# Pico.net
KiCad netlist of a schematic drawn in Altium Designer
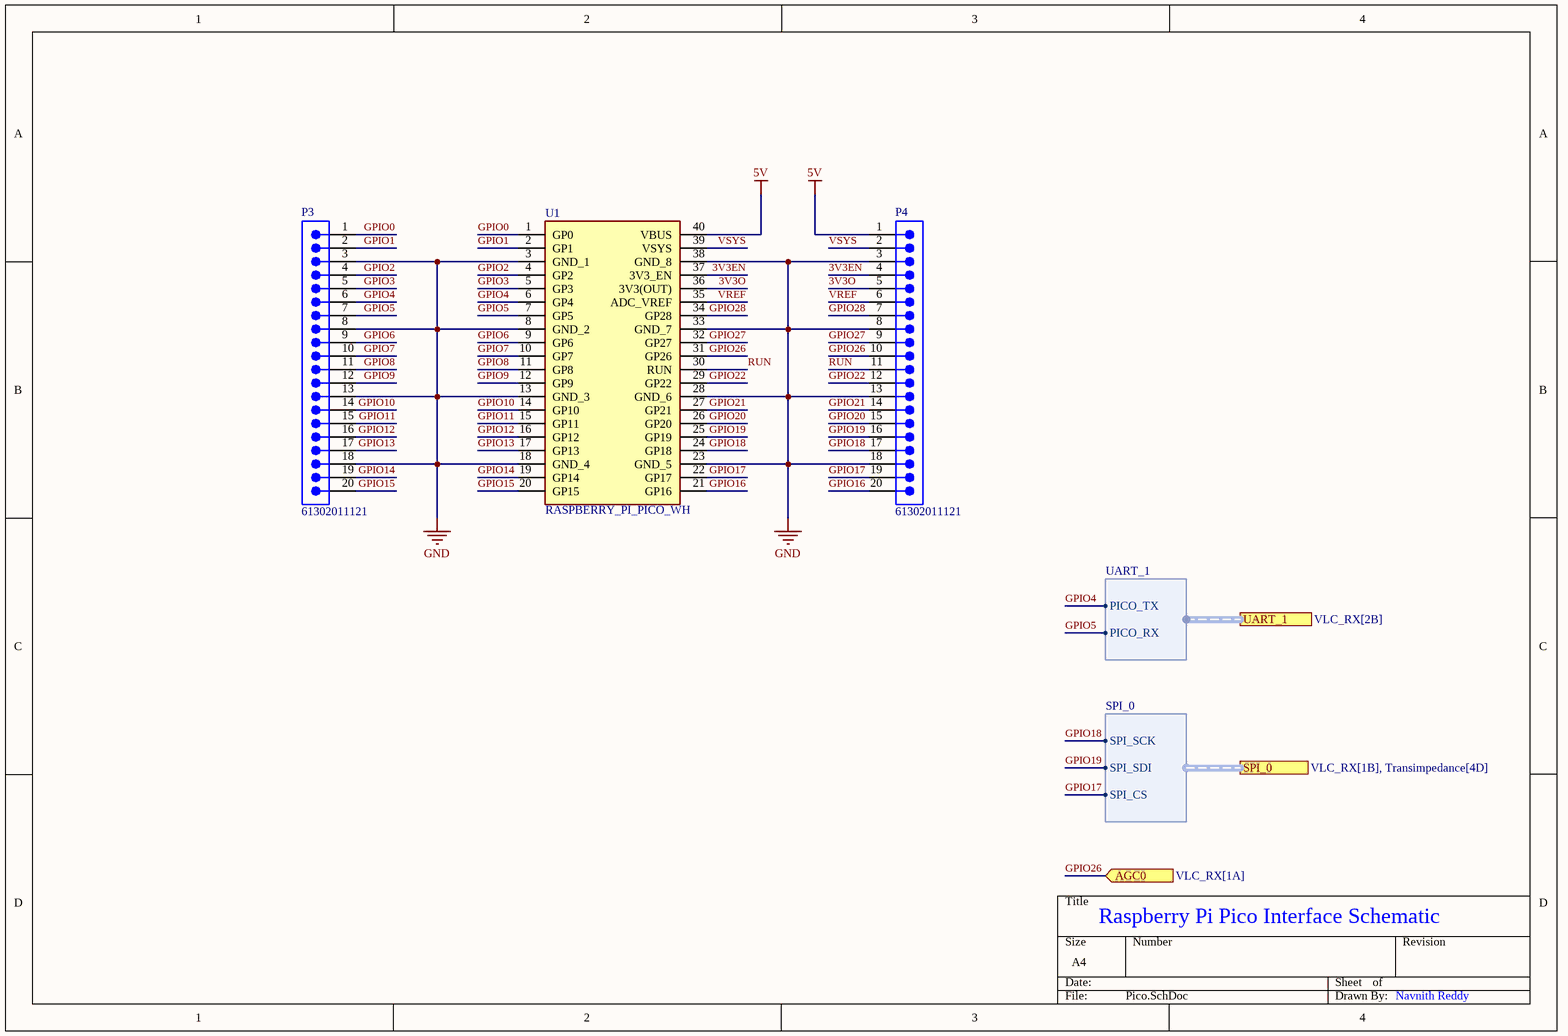
[diagram p0: Pico.SchDoc]

(export (version "E")
  (design (tool "Eeschema 10.0.6"))
  (components
    (comp (ref "P3")
      (value "61302011121")
      (footprint "61302011121")
      (libsource (lib "Altium Content Vault") (part "Header_Male_1R_20P"))
    )
    (comp (ref "P4")
      (value "61302011121")
      (footprint "61302011121")
      (libsource (lib "Altium Content Vault") (part "Header_Male_1R_20P"))
    )
    (comp (ref "U1")
      (value "RASPBERRY_PI_PICO_WH")
      (footprint "SamacSys:RASPBERRYPIPICOWH")
      (description "Undefined or Miscellaneous")
      (fields (field (name "MANUFACTURER_PART_NUMBER") "RASPBERRY PI PICO WH"))
      (libsource (lib "*") (part "RASPBERRY_PI_PICO_WH"))
    )
  )
  (nets
    (net (code "3") (name "/3V3EN") (class "Default")
      (node (ref "P4") (pin "4") (pinfunction "4_4") (pintype "passive"))
      (node (ref "U1") (pin "37") (pinfunction "3V3_EN_37") (pintype "passive"))
    )
    (net (code "4") (name "/3V3O") (class "Default")
      (node (ref "P4") (pin "5") (pinfunction "5_5") (pintype "passive"))
      (node (ref "U1") (pin "36") (pinfunction "3V3(OUT)_36") (pintype "passive"))
    )
    (net (code "5") (name "/GPIO0") (class "Default")
      (node (ref "P3") (pin "1") (pinfunction "1_1") (pintype "passive"))
      (node (ref "U1") (pin "1") (pinfunction "GP0_1") (pintype "passive"))
    )
    (net (code "6") (name "/GPIO1") (class "Default")
      (node (ref "P3") (pin "2") (pinfunction "2_2") (pintype "passive"))
      (node (ref "U1") (pin "2") (pinfunction "GP1_2") (pintype "passive"))
    )
    (net (code "7") (name "/GPIO2") (class "Default")
      (node (ref "P3") (pin "4") (pinfunction "4_4") (pintype "passive"))
      (node (ref "U1") (pin "4") (pinfunction "GP2_4") (pintype "passive"))
    )
    (net (code "8") (name "/GPIO3") (class "Default")
      (node (ref "P3") (pin "5") (pinfunction "5_5") (pintype "passive"))
      (node (ref "U1") (pin "5") (pinfunction "GP3_5") (pintype "passive"))
    )
    (net (code "9") (name "/GPIO4") (class "Default")
      (node (ref "P3") (pin "6") (pinfunction "6_6") (pintype "passive"))
      (node (ref "U1") (pin "6") (pinfunction "GP4_6") (pintype "passive"))
    )
    (net (code "10") (name "/GPIO5") (class "Default")
      (node (ref "P3") (pin "7") (pinfunction "7_7") (pintype "passive"))
      (node (ref "U1") (pin "7") (pinfunction "GP5_7") (pintype "passive"))
    )
    (net (code "11") (name "/GPIO6") (class "Default")
      (node (ref "P3") (pin "9") (pinfunction "9_9") (pintype "passive"))
      (node (ref "U1") (pin "9") (pinfunction "GP6_9") (pintype "passive"))
    )
    (net (code "12") (name "/GPIO7") (class "Default")
      (node (ref "P3") (pin "10") (pinfunction "10_10") (pintype "passive"))
      (node (ref "U1") (pin "10") (pinfunction "GP7_10") (pintype "passive"))
    )
    (net (code "13") (name "/GPIO8") (class "Default")
      (node (ref "P3") (pin "11") (pinfunction "11_11") (pintype "passive"))
      (node (ref "U1") (pin "11") (pinfunction "GP8_11") (pintype "passive"))
    )
    (net (code "14") (name "/GPIO9") (class "Default")
      (node (ref "P3") (pin "12") (pinfunction "12_12") (pintype "passive"))
      (node (ref "U1") (pin "12") (pinfunction "GP9_12") (pintype "passive"))
    )
    (net (code "15") (name "/GPIO10") (class "Default")
      (node (ref "P3") (pin "14") (pinfunction "14_14") (pintype "passive"))
      (node (ref "U1") (pin "14") (pinfunction "GP10_14") (pintype "passive"))
    )
    (net (code "16") (name "/GPIO11") (class "Default")
      (node (ref "P3") (pin "15") (pinfunction "15_15") (pintype "passive"))
      (node (ref "U1") (pin "15") (pinfunction "GP11_15") (pintype "passive"))
    )
    (net (code "17") (name "/GPIO12") (class "Default")
      (node (ref "P3") (pin "16") (pinfunction "16_16") (pintype "passive"))
      (node (ref "U1") (pin "16") (pinfunction "GP12_16") (pintype "passive"))
    )
    (net (code "18") (name "/GPIO13") (class "Default")
      (node (ref "P3") (pin "17") (pinfunction "17_17") (pintype "passive"))
      (node (ref "U1") (pin "17") (pinfunction "GP13_17") (pintype "passive"))
    )
    (net (code "19") (name "/GPIO14") (class "Default")
      (node (ref "P3") (pin "19") (pinfunction "19_19") (pintype "passive"))
      (node (ref "U1") (pin "19") (pinfunction "GP14_19") (pintype "passive"))
    )
    (net (code "20") (name "/GPIO15") (class "Default")
      (node (ref "P3") (pin "20") (pinfunction "20_20") (pintype "passive"))
      (node (ref "U1") (pin "20") (pinfunction "GP15_20") (pintype "passive"))
    )
    (net (code "21") (name "/GPIO16") (class "Default")
      (node (ref "P4") (pin "20") (pinfunction "20_20") (pintype "passive"))
      (node (ref "U1") (pin "21") (pinfunction "GP16_21") (pintype "passive"))
    )
    (net (code "22") (name "/GPIO17") (class "Default")
      (node (ref "P4") (pin "19") (pinfunction "19_19") (pintype "passive"))
      (node (ref "U1") (pin "22") (pinfunction "GP17_22") (pintype "passive"))
    )
    (net (code "23") (name "/GPIO18") (class "Default")
      (node (ref "P4") (pin "17") (pinfunction "17_17") (pintype "passive"))
      (node (ref "U1") (pin "24") (pinfunction "GP18_24") (pintype "passive"))
    )
    (net (code "24") (name "/GPIO19") (class "Default")
      (node (ref "P4") (pin "16") (pinfunction "16_16") (pintype "passive"))
      (node (ref "U1") (pin "25") (pinfunction "GP19_25") (pintype "passive"))
    )
    (net (code "25") (name "/GPIO20") (class "Default")
      (node (ref "P4") (pin "15") (pinfunction "15_15") (pintype "passive"))
      (node (ref "U1") (pin "26") (pinfunction "GP20_26") (pintype "passive"))
    )
    (net (code "26") (name "/GPIO21") (class "Default")
      (node (ref "P4") (pin "14") (pinfunction "14_14") (pintype "passive"))
      (node (ref "U1") (pin "27") (pinfunction "GP21_27") (pintype "passive"))
    )
    (net (code "27") (name "/GPIO22") (class "Default")
      (node (ref "P4") (pin "12") (pinfunction "12_12") (pintype "passive"))
      (node (ref "U1") (pin "29") (pinfunction "GP22_29") (pintype "passive"))
    )
    (net (code "28") (name "/GPIO26") (class "Default")
      (node (ref "P4") (pin "10") (pinfunction "10_10") (pintype "passive"))
      (node (ref "U1") (pin "31") (pinfunction "GP26_31") (pintype "passive"))
    )
    (net (code "29") (name "/GPIO27") (class "Default")
      (node (ref "P4") (pin "9") (pinfunction "9_9") (pintype "passive"))
      (node (ref "U1") (pin "32") (pinfunction "GP27_32") (pintype "passive"))
    )
    (net (code "30") (name "/GPIO28") (class "Default")
      (node (ref "P4") (pin "7") (pinfunction "7_7") (pintype "passive"))
      (node (ref "U1") (pin "34") (pinfunction "GP28_34") (pintype "passive"))
    )
    (net (code "31") (name "/RUN") (class "Default")
      (node (ref "P4") (pin "11") (pinfunction "11_11") (pintype "passive"))
      (node (ref "U1") (pin "30") (pinfunction "RUN_30") (pintype "passive"))
    )
    (net (code "32") (name "/VREF") (class "Default")
      (node (ref "P4") (pin "6") (pinfunction "6_6") (pintype "passive"))
      (node (ref "U1") (pin "35") (pinfunction "ADC_VREF_35") (pintype "passive"))
    )
    (net (code "33") (name "/VSYS") (class "Default")
      (node (ref "P4") (pin "2") (pinfunction "2_2") (pintype "passive"))
      (node (ref "U1") (pin "39") (pinfunction "VSYS_39") (pintype "passive"))
    )
    (net (code "36") (name "5V") (class "Default")
      (node (ref "P4") (pin "1") (pinfunction "1_1") (pintype "passive"))
      (node (ref "U1") (pin "40") (pinfunction "VBUS_40") (pintype "passive"))
    )
    (net (code "37") (name "GND") (class "Default")
      (node (ref "P3") (pin "13") (pinfunction "13_13") (pintype "passive"))
      (node (ref "P3") (pin "18") (pinfunction "18_18") (pintype "passive"))
      (node (ref "P3") (pin "3") (pinfunction "3_3") (pintype "passive"))
      (node (ref "P3") (pin "8") (pinfunction "8_8") (pintype "passive"))
      (node (ref "P4") (pin "13") (pinfunction "13_13") (pintype "passive"))
      (node (ref "P4") (pin "18") (pinfunction "18_18") (pintype "passive"))
      (node (ref "P4") (pin "3") (pinfunction "3_3") (pintype "passive"))
      (node (ref "P4") (pin "8") (pinfunction "8_8") (pintype "passive"))
      (node (ref "U1") (pin "13") (pinfunction "GND_3_13") (pintype "passive"))
      (node (ref "U1") (pin "18") (pinfunction "GND_4_18") (pintype "passive"))
      (node (ref "U1") (pin "23") (pinfunction "GND_5_23") (pintype "passive"))
      (node (ref "U1") (pin "28") (pinfunction "GND_6_28") (pintype "passive"))
      (node (ref "U1") (pin "3") (pinfunction "GND_1_3") (pintype "passive"))
      (node (ref "U1") (pin "33") (pinfunction "GND_7_33") (pintype "passive"))
      (node (ref "U1") (pin "38") (pinfunction "GND_8_38") (pintype "passive"))
      (node (ref "U1") (pin "8") (pinfunction "GND_2_8") (pintype "passive"))
    )
  )
)
